# div_mod.net
KiCad netlist of a schematic drawn in EAGLE
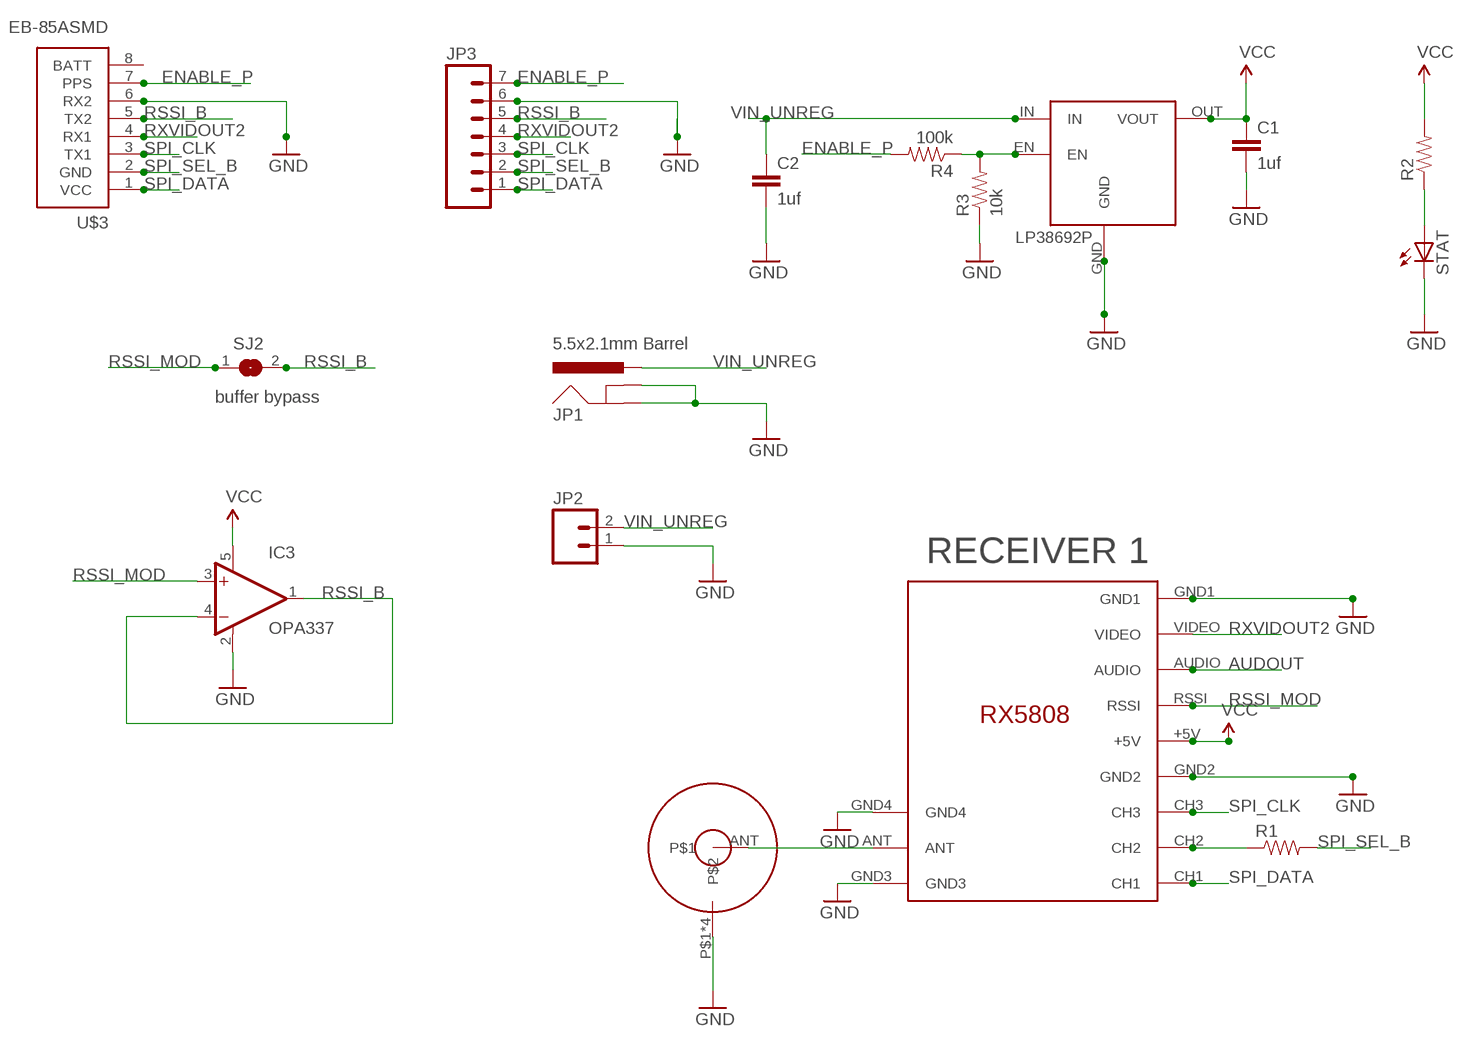
[diagram p0: schematic, sheet 1]

(export (version "E")
  (design (tool "Eeschema 10.0.6"))
  (components
    (comp (ref "C1")
      (value "1uf")
      (footprint "eagle-import:0805")
      (libsource (lib "eagle-import") (part "CAP0805"))
    )
    (comp (ref "C2")
      (value "1uf")
      (footprint "eagle-import:0805")
      (libsource (lib "eagle-import") (part "CAP0805"))
    )
    (comp (ref "IC3")
      (value "OPA336N")
      (footprint "eagle-import:SOT23-5")
      (fields (field (name "MPN") "OPA336NA"))
      (libsource (lib "eagle-import") (part "OPA336N"))
    )
    (comp (ref "JP1")
      (value "5.5x2.1mm Barrel")
      (footprint "eagle-import:POWER_JACK_SMD")
      (libsource (lib "eagle-import") (part "POWER_JACKSMD"))
    )
    (comp (ref "JP2")
      (value "M02PTH")
      (footprint "eagle-import:1X02")
      (libsource (lib "eagle-import") (part "M02PTH"))
    )
    (comp (ref "JP3")
      (value "M07")
      (footprint "eagle-import:1X07")
      (libsource (lib "eagle-import") (part "M07"))
    )
    (comp (ref "R1")
      (value "RESISTOR0805-RES")
      (footprint "eagle-import:0805")
      (libsource (lib "eagle-import") (part "RESISTOR0805-RES"))
    )
    (comp (ref "R2")
      (value "RESISTOR0805-RES")
      (footprint "eagle-import:0805")
      (libsource (lib "eagle-import") (part "RESISTOR0805-RES"))
    )
    (comp (ref "R3")
      (value "10k")
      (footprint "eagle-import:0805")
      (libsource (lib "eagle-import") (part "RESISTOR0805-RES"))
    )
    (comp (ref "R4")
      (value "100k")
      (footprint "eagle-import:0805")
      (libsource (lib "eagle-import") (part "RESISTOR0805-RES"))
    )
    (comp (ref "RECEIVER_A")
      (value "RX5808_A")
      (footprint "eagle-import:RX5808")
      (libsource (lib "eagle-import") (part "RX5808"))
    )
    (comp (ref "SJ2") (value "SJ") (footprint "eagle-import:SJ") (libsource (lib "eagle-import") (part "SJ")))
    (comp (ref "STAT")
      (value "LEDCHIP-LED0805")
      (footprint "eagle-import:CHIP-LED0805")
      (libsource (lib "eagle-import") (part "LEDCHIP-LED0805"))
    )
    (comp (ref "U$1")
      (value "SMA_ANTENNA")
      (footprint "eagle-import:SMA_CONNECTOR")
      (libsource (lib "eagle-import") (part "SMA_ANTENNA"))
    )
    (comp (ref "U$3")
      (value "EB-85ASMD")
      (footprint "eagle-import:EB-85A")
      (libsource (lib "eagle-import") (part "EB-85ASMD"))
    )
    (comp (ref "V1")
      (value "LP38692P")
      (footprint "eagle-import:TO252-51")
      (libsource (lib "eagle-import") (part "LP38692P"))
    )
  )
  (nets
    (net (code "1") (name "/AUDOUT") (class "Default")
      (node (ref "RECEIVER_A") (pin "AUDIO") (pinfunction "AUDIO_AUDIO") (pintype "bidirectional"))
    )
    (net (code "2") (name "/BATT") (class "Default")
      (node (ref "U$3") (pin "8") (pinfunction "BATT_8") (pintype "power_in"))
    )
    (net (code "3") (name "/ENABLE_P") (class "Default")
      (node (ref "JP3") (pin "7") (pinfunction "7_7") (pintype "passive"))
      (node (ref "R4") (pin "2") (pinfunction "2_2") (pintype "passive"))
      (node (ref "U$3") (pin "7") (pinfunction "PPS_7") (pintype "output"))
    )
    (net (code "4") (name "/RSSI_B") (class "Default")
      (node (ref "IC3") (pin "1") (pinfunction "OUT_1") (pintype "output"))
      (node (ref "IC3") (pin "4") (pinfunction "-IN_4") (pintype "input"))
      (node (ref "JP3") (pin "5") (pinfunction "5_5") (pintype "passive"))
      (node (ref "SJ2") (pin "2") (pinfunction "2_2") (pintype "passive"))
      (node (ref "U$3") (pin "5") (pinfunction "TX2_5") (pintype "output"))
    )
    (net (code "5") (name "/RSSI_MOD") (class "Default")
      (node (ref "IC3") (pin "3") (pinfunction "+IN_3") (pintype "input"))
      (node (ref "RECEIVER_A") (pin "RSSI") (pinfunction "RSSI_RSSI") (pintype "bidirectional"))
      (node (ref "SJ2") (pin "1") (pinfunction "1_1") (pintype "passive"))
    )
    (net (code "6") (name "/RXVIDOUT2") (class "Default")
      (node (ref "JP3") (pin "4") (pinfunction "4_4") (pintype "passive"))
      (node (ref "RECEIVER_A") (pin "VIDEO") (pinfunction "VIDEO_VIDEO") (pintype "bidirectional"))
      (node (ref "U$3") (pin "4") (pinfunction "RX1_4") (pintype "input"))
    )
    (net (code "7") (name "/SPI_CLK") (class "Default")
      (node (ref "JP3") (pin "3") (pinfunction "3_3") (pintype "passive"))
      (node (ref "RECEIVER_A") (pin "CH3") (pinfunction "CH3_CH3") (pintype "bidirectional"))
      (node (ref "U$3") (pin "3") (pinfunction "TX1_3") (pintype "output"))
    )
    (net (code "8") (name "/SPI_DATA") (class "Default")
      (node (ref "JP3") (pin "1") (pinfunction "1_1") (pintype "passive"))
      (node (ref "RECEIVER_A") (pin "CH1") (pinfunction "CH1_CH1") (pintype "bidirectional"))
      (node (ref "U$3") (pin "1") (pinfunction "VCC_1") (pintype "power_in"))
    )
    (net (code "9") (name "/SPI_SEL_B") (class "Default")
      (node (ref "JP3") (pin "2") (pinfunction "2_2") (pintype "passive"))
      (node (ref "R1") (pin "2") (pinfunction "2_2") (pintype "passive"))
      (node (ref "U$3") (pin "2") (pinfunction "GND_2") (pintype "power_in"))
    )
    (net (code "10") (name "/VIN_UNREG") (class "Default")
      (node (ref "C2") (pin "1") (pinfunction "1_1") (pintype "passive"))
      (node (ref "JP1") (pin "VIN0") (pinfunction "PWR_VIN0") (pintype "bidirectional"))
      (node (ref "JP2") (pin "2") (pinfunction "2_2") (pintype "passive"))
      (node (ref "V1") (pin "IN") (pinfunction "IN_IN") (pintype "bidirectional"))
    )
    (net (code "11") (name "GND") (class "Default")
      (node (ref "C1") (pin "2") (pinfunction "2_2") (pintype "passive"))
      (node (ref "C2") (pin "2") (pinfunction "2_2") (pintype "passive"))
      (node (ref "IC3") (pin "2") (pinfunction "V-_2") (pintype "power_in"))
      (node (ref "JP1") (pin "GND") (pinfunction "GNDBREAK_GND") (pintype "bidirectional"))
      (node (ref "JP1") (pin "P$4") (pinfunction "GND_P$4") (pintype "bidirectional"))
      (node (ref "JP2") (pin "1") (pinfunction "1_1") (pintype "passive"))
      (node (ref "JP3") (pin "6") (pinfunction "6_6") (pintype "passive"))
      (node (ref "R3") (pin "1") (pinfunction "1_1") (pintype "passive"))
      (node (ref "RECEIVER_A") (pin "GND1") (pinfunction "GND1_GND1") (pintype "bidirectional"))
      (node (ref "RECEIVER_A") (pin "GND2") (pinfunction "GND2_GND2") (pintype "bidirectional"))
      (node (ref "RECEIVER_A") (pin "GND3") (pinfunction "GND3_GND3") (pintype "bidirectional"))
      (node (ref "RECEIVER_A") (pin "GND4") (pinfunction "GND4_GND4") (pintype "bidirectional"))
      (node (ref "STAT") (pin "C") (pinfunction "C_C") (pintype "passive"))
      (node (ref "U$1") (pin "P$1") (pinfunction "P$2_P$1") (pintype "bidirectional"))
      (node (ref "U$1") (pin "P$2") (pinfunction "P$2_P$2") (pintype "bidirectional"))
      (node (ref "U$1") (pin "P$3") (pinfunction "P$2_P$3") (pintype "bidirectional"))
      (node (ref "U$1") (pin "P$4") (pinfunction "P$2_P$4") (pintype "bidirectional"))
      (node (ref "U$3") (pin "6") (pinfunction "RX2_6") (pintype "input"))
      (node (ref "V1") (pin "GND") (pinfunction "GND_GND") (pintype "bidirectional"))
    )
    (net (code "12") (name "Net-(R1-Pad1)") (class "Default")
      (node (ref "R1") (pin "1") (pinfunction "1_1") (pintype "passive"))
      (node (ref "RECEIVER_A") (pin "CH2") (pinfunction "CH2_CH2") (pintype "bidirectional"))
    )
    (net (code "13") (name "Net-(R2-Pad1)") (class "Default")
      (node (ref "R2") (pin "1") (pinfunction "1_1") (pintype "passive"))
      (node (ref "STAT") (pin "A") (pinfunction "A_A") (pintype "passive"))
    )
    (net (code "14") (name "Net-(R3-Pad2)") (class "Default")
      (node (ref "R3") (pin "2") (pinfunction "2_2") (pintype "passive"))
      (node (ref "R4") (pin "1") (pinfunction "1_1") (pintype "passive"))
      (node (ref "V1") (pin "EN") (pinfunction "EN_EN") (pintype "bidirectional"))
    )
    (net (code "15") (name "Net-(U$1-P$1)") (class "Default")
      (node (ref "RECEIVER_A") (pin "ANT") (pinfunction "ANT_ANT") (pintype "bidirectional"))
      (node (ref "U$1") (pin "ANT") (pinfunction "P$1_ANT") (pintype "bidirectional"))
    )
    (net (code "16") (name "VCC") (class "Default")
      (node (ref "C1") (pin "1") (pinfunction "1_1") (pintype "passive"))
      (node (ref "IC3") (pin "5") (pinfunction "V+_5") (pintype "power_in"))
      (node (ref "R2") (pin "2") (pinfunction "2_2") (pintype "passive"))
      (node (ref "RECEIVER_A") (pin "+5V") (pinfunction "+5V_+5V") (pintype "bidirectional"))
      (node (ref "V1") (pin "OUT") (pinfunction "VOUT_OUT") (pintype "bidirectional"))
    )
  )
)
